# DoublePN-03092017-001.net
KiCad netlist of a schematic drawn in EAGLE
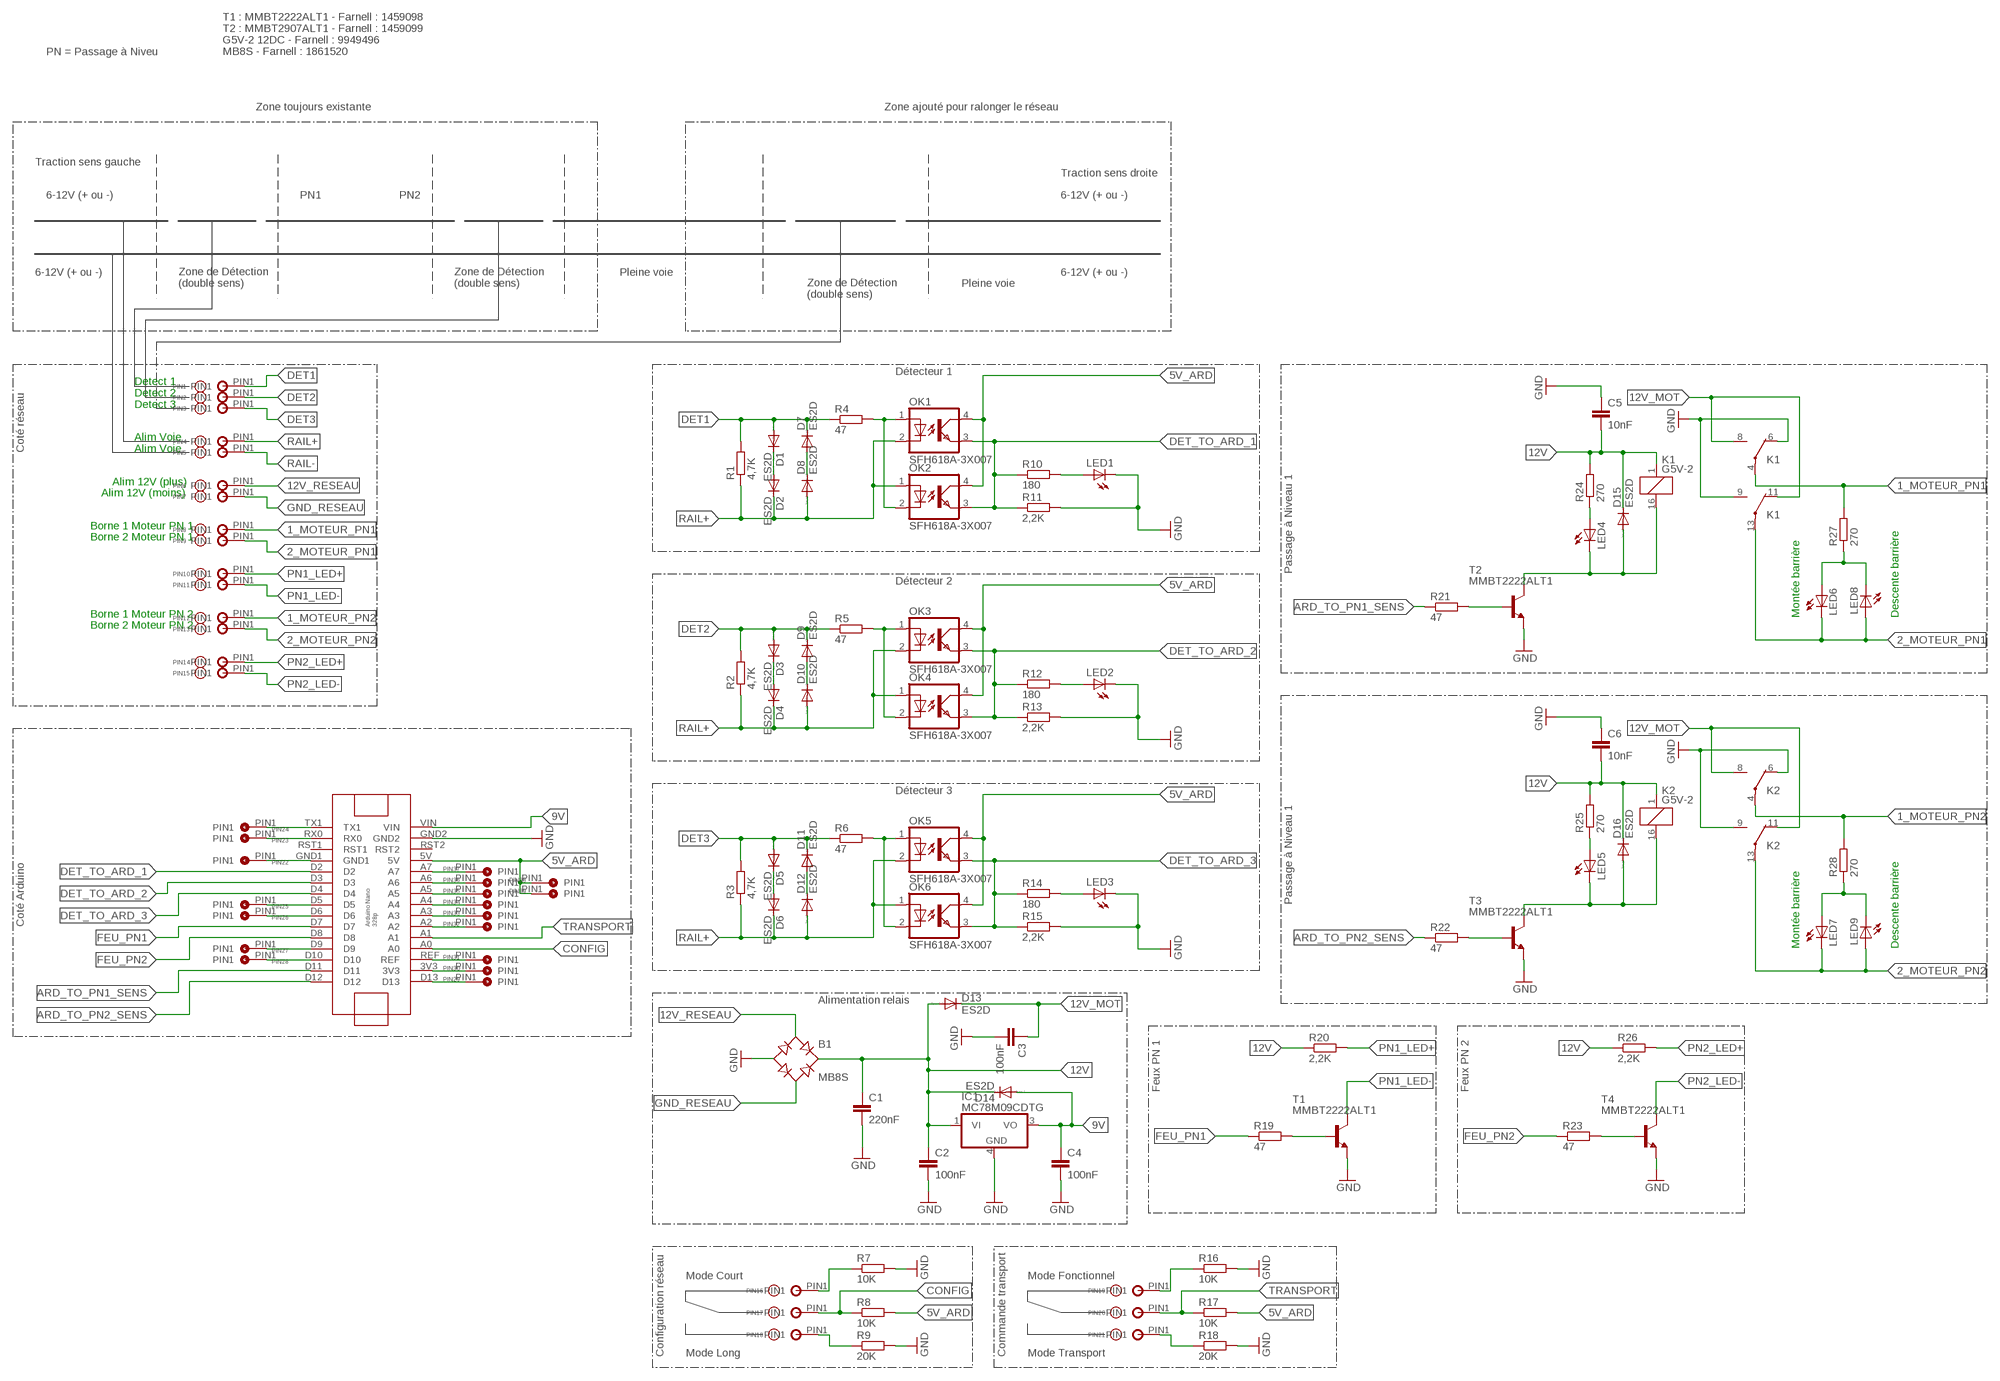
[diagram p0: schematic, sheet 1]

(export (version "E")
  (design (tool "Eeschema 10.0.6"))
  (components
    (comp (ref "ARDUINO-NANO1")
      (value "ARDUINO-NANO")
      (footprint "eagle-import:ARDUINO-NANO")
      (libsource (lib "eagle-import") (part "ARDUINO-NANO"))
    )
    (comp (ref "B1")
      (value "MB8S")
      (footprint "eagle-import:SOIC-4")
      (libsource (lib "eagle-import") (part "MBS8"))
    )
    (comp (ref "C1")
      (value "220nF")
      (footprint "eagle-import:C0805")
      (libsource (lib "eagle-import") (part "C-EUC0805"))
    )
    (comp (ref "C2")
      (value "100nF")
      (footprint "eagle-import:C0805")
      (libsource (lib "eagle-import") (part "C-EUC0805"))
    )
    (comp (ref "C3")
      (value "100nF")
      (footprint "eagle-import:C0805")
      (libsource (lib "eagle-import") (part "C-EUC0805"))
    )
    (comp (ref "C4")
      (value "100nF")
      (footprint "eagle-import:C0805")
      (libsource (lib "eagle-import") (part "C-EUC0805"))
    )
    (comp (ref "C5")
      (value "10nF")
      (footprint "eagle-import:C0805")
      (libsource (lib "eagle-import") (part "C-EUC0805"))
    )
    (comp (ref "C6")
      (value "10nF")
      (footprint "eagle-import:C0805")
      (libsource (lib "eagle-import") (part "C-EUC0805"))
    )
    (comp (ref "D1")
      (value "ES2D")
      (footprint "eagle-import:SMB")
      (libsource (lib "eagle-import") (part "ES2D"))
    )
    (comp (ref "D2")
      (value "ES2D")
      (footprint "eagle-import:SMB")
      (libsource (lib "eagle-import") (part "ES2D"))
    )
    (comp (ref "D3")
      (value "ES2D")
      (footprint "eagle-import:SMB")
      (libsource (lib "eagle-import") (part "ES2D"))
    )
    (comp (ref "D4")
      (value "ES2D")
      (footprint "eagle-import:SMB")
      (libsource (lib "eagle-import") (part "ES2D"))
    )
    (comp (ref "D5")
      (value "ES2D")
      (footprint "eagle-import:SMB")
      (libsource (lib "eagle-import") (part "ES2D"))
    )
    (comp (ref "D6")
      (value "ES2D")
      (footprint "eagle-import:SMB")
      (libsource (lib "eagle-import") (part "ES2D"))
    )
    (comp (ref "D7")
      (value "ES2D")
      (footprint "eagle-import:SMB")
      (libsource (lib "eagle-import") (part "ES2D"))
    )
    (comp (ref "D8")
      (value "ES2D")
      (footprint "eagle-import:SMB")
      (libsource (lib "eagle-import") (part "ES2D"))
    )
    (comp (ref "D9")
      (value "ES2D")
      (footprint "eagle-import:SMB")
      (libsource (lib "eagle-import") (part "ES2D"))
    )
    (comp (ref "D10")
      (value "ES2D")
      (footprint "eagle-import:SMB")
      (libsource (lib "eagle-import") (part "ES2D"))
    )
    (comp (ref "D11")
      (value "ES2D")
      (footprint "eagle-import:SMB")
      (libsource (lib "eagle-import") (part "ES2D"))
    )
    (comp (ref "D12")
      (value "ES2D")
      (footprint "eagle-import:SMB")
      (libsource (lib "eagle-import") (part "ES2D"))
    )
    (comp (ref "D13")
      (value "ES2D")
      (footprint "eagle-import:SMB")
      (libsource (lib "eagle-import") (part "ES2D"))
    )
    (comp (ref "D14")
      (value "ES2D")
      (footprint "eagle-import:SMB")
      (libsource (lib "eagle-import") (part "ES2D"))
    )
    (comp (ref "D15")
      (value "ES2D")
      (footprint "eagle-import:SMB")
      (libsource (lib "eagle-import") (part "ES2D"))
    )
    (comp (ref "D16")
      (value "ES2D")
      (footprint "eagle-import:SMB")
      (libsource (lib "eagle-import") (part "ES2D"))
    )
    (comp (ref "IC1")
      (value "MC78M09CDTG")
      (footprint "eagle-import:DPACK_3")
      (libsource (lib "eagle-import") (part "MC78M09CDTG"))
    )
    (comp (ref "K1")
      (value "G5V-2")
      (footprint "eagle-import:G5V-2")
      (fields (field (name "MPN") "G5V-2 5DC"))
      (libsource (lib "eagle-import") (part "G5V-2"))
    )
    (comp (ref "K2")
      (value "G5V-2")
      (footprint "eagle-import:G5V-2")
      (fields (field (name "MPN") "G5V-2 5DC"))
      (libsource (lib "eagle-import") (part "G5V-2"))
    )
    (comp (ref "LED1")
      (value "LEDCHIPLED_0805")
      (footprint "eagle-import:CHIPLED_0805")
      (libsource (lib "eagle-import") (part "LEDCHIPLED_0805"))
    )
    (comp (ref "LED2")
      (value "LEDCHIPLED_0805")
      (footprint "eagle-import:CHIPLED_0805")
      (libsource (lib "eagle-import") (part "LEDCHIPLED_0805"))
    )
    (comp (ref "LED3")
      (value "LEDCHIPLED_0805")
      (footprint "eagle-import:CHIPLED_0805")
      (libsource (lib "eagle-import") (part "LEDCHIPLED_0805"))
    )
    (comp (ref "LED4")
      (value "LEDCHIPLED_0805")
      (footprint "eagle-import:CHIPLED_0805")
      (libsource (lib "eagle-import") (part "LEDCHIPLED_0805"))
    )
    (comp (ref "LED5")
      (value "LEDCHIPLED_0805")
      (footprint "eagle-import:CHIPLED_0805")
      (libsource (lib "eagle-import") (part "LEDCHIPLED_0805"))
    )
    (comp (ref "LED6")
      (value "LEDCHIPLED_0805")
      (footprint "eagle-import:CHIPLED_0805")
      (libsource (lib "eagle-import") (part "LEDCHIPLED_0805"))
    )
    (comp (ref "LED7")
      (value "LEDCHIPLED_0805")
      (footprint "eagle-import:CHIPLED_0805")
      (libsource (lib "eagle-import") (part "LEDCHIPLED_0805"))
    )
    (comp (ref "LED8")
      (value "LEDCHIPLED_0805")
      (footprint "eagle-import:CHIPLED_0805")
      (libsource (lib "eagle-import") (part "LEDCHIPLED_0805"))
    )
    (comp (ref "LED9")
      (value "LEDCHIPLED_0805")
      (footprint "eagle-import:CHIPLED_0805")
      (libsource (lib "eagle-import") (part "LEDCHIPLED_0805"))
    )
    (comp (ref "OK1")
      (value "SFH618A-3X007")
      (footprint "eagle-import:SMD4-7")
      (libsource (lib "eagle-import") (part "SFH618?A-3X007"))
    )
    (comp (ref "OK2")
      (value "SFH618A-3X007")
      (footprint "eagle-import:SMD4-7")
      (libsource (lib "eagle-import") (part "SFH618?A-3X007"))
    )
    (comp (ref "OK3")
      (value "SFH618A-3X007")
      (footprint "eagle-import:SMD4-7")
      (libsource (lib "eagle-import") (part "SFH618?A-3X007"))
    )
    (comp (ref "OK4")
      (value "SFH618A-3X007")
      (footprint "eagle-import:SMD4-7")
      (libsource (lib "eagle-import") (part "SFH618?A-3X007"))
    )
    (comp (ref "OK5")
      (value "SFH618A-3X007")
      (footprint "eagle-import:SMD4-7")
      (libsource (lib "eagle-import") (part "SFH618?A-3X007"))
    )
    (comp (ref "OK6")
      (value "SFH618A-3X007")
      (footprint "eagle-import:SMD4-7")
      (libsource (lib "eagle-import") (part "SFH618?A-3X007"))
    )
    (comp (ref "PIN1")
      (value "CON-FILTRAVERSANT-1FILTRAVERSANT-1")
      (footprint "eagle-import:CON-FILTRAVERSANT-1")
      (libsource (lib "eagle-import") (part "CON-FILTRAVERSANT-1FILTRAVERSANT-1"))
    )
    (comp (ref "PIN2")
      (value "CON-FILTRAVERSANT-1FILTRAVERSANT-1")
      (footprint "eagle-import:CON-FILTRAVERSANT-1")
      (libsource (lib "eagle-import") (part "CON-FILTRAVERSANT-1FILTRAVERSANT-1"))
    )
    (comp (ref "PIN3")
      (value "CON-FILTRAVERSANT-1FILTRAVERSANT-1")
      (footprint "eagle-import:CON-FILTRAVERSANT-1")
      (libsource (lib "eagle-import") (part "CON-FILTRAVERSANT-1FILTRAVERSANT-1"))
    )
    (comp (ref "PIN4")
      (value "CON-FILTRAVERSANT-1FILTRAVERSANT-1")
      (footprint "eagle-import:CON-FILTRAVERSANT-1")
      (libsource (lib "eagle-import") (part "CON-FILTRAVERSANT-1FILTRAVERSANT-1"))
    )
    (comp (ref "PIN5")
      (value "CON-FILTRAVERSANT-1FILTRAVERSANT-1")
      (footprint "eagle-import:CON-FILTRAVERSANT-1")
      (libsource (lib "eagle-import") (part "CON-FILTRAVERSANT-1FILTRAVERSANT-1"))
    )
    (comp (ref "PIN6")
      (value "CON-FILTRAVERSANT-1FILTRAVERSANT-1")
      (footprint "eagle-import:CON-FILTRAVERSANT-1")
      (libsource (lib "eagle-import") (part "CON-FILTRAVERSANT-1FILTRAVERSANT-1"))
    )
    (comp (ref "PIN7")
      (value "CON-FILTRAVERSANT-1FILTRAVERSANT-1")
      (footprint "eagle-import:CON-FILTRAVERSANT-1")
      (libsource (lib "eagle-import") (part "CON-FILTRAVERSANT-1FILTRAVERSANT-1"))
    )
    (comp (ref "PIN8")
      (value "CON-FILTRAVERSANT-1FILTRAVERSANT-1")
      (footprint "eagle-import:CON-FILTRAVERSANT-1")
      (libsource (lib "eagle-import") (part "CON-FILTRAVERSANT-1FILTRAVERSANT-1"))
    )
    (comp (ref "PIN9")
      (value "CON-FILTRAVERSANT-1FILTRAVERSANT-1")
      (footprint "eagle-import:CON-FILTRAVERSANT-1")
      (libsource (lib "eagle-import") (part "CON-FILTRAVERSANT-1FILTRAVERSANT-1"))
    )
    (comp (ref "PIN10")
      (value "CON-FILTRAVERSANT-1FILTRAVERSANT-1")
      (footprint "eagle-import:CON-FILTRAVERSANT-1")
      (libsource (lib "eagle-import") (part "CON-FILTRAVERSANT-1FILTRAVERSANT-1"))
    )
    (comp (ref "PIN11")
      (value "CON-FILTRAVERSANT-1FILTRAVERSANT-1")
      (footprint "eagle-import:CON-FILTRAVERSANT-1")
      (libsource (lib "eagle-import") (part "CON-FILTRAVERSANT-1FILTRAVERSANT-1"))
    )
    (comp (ref "PIN12")
      (value "CON-FILTRAVERSANT-1FILTRAVERSANT-1")
      (footprint "eagle-import:CON-FILTRAVERSANT-1")
      (libsource (lib "eagle-import") (part "CON-FILTRAVERSANT-1FILTRAVERSANT-1"))
    )
    (comp (ref "PIN13")
      (value "CON-FILTRAVERSANT-1FILTRAVERSANT-1")
      (footprint "eagle-import:CON-FILTRAVERSANT-1")
      (libsource (lib "eagle-import") (part "CON-FILTRAVERSANT-1FILTRAVERSANT-1"))
    )
    (comp (ref "PIN14")
      (value "CON-FILTRAVERSANT-1FILTRAVERSANT-1")
      (footprint "eagle-import:CON-FILTRAVERSANT-1")
      (libsource (lib "eagle-import") (part "CON-FILTRAVERSANT-1FILTRAVERSANT-1"))
    )
    (comp (ref "PIN15")
      (value "CON-FILTRAVERSANT-1FILTRAVERSANT-1")
      (footprint "eagle-import:CON-FILTRAVERSANT-1")
      (libsource (lib "eagle-import") (part "CON-FILTRAVERSANT-1FILTRAVERSANT-1"))
    )
    (comp (ref "PIN16")
      (value "CON-FILTRAVERSANT-1FILTRAVERSANT-1")
      (footprint "eagle-import:CON-FILTRAVERSANT-1")
      (libsource (lib "eagle-import") (part "CON-FILTRAVERSANT-1FILTRAVERSANT-1"))
    )
    (comp (ref "PIN17")
      (value "CON-FILTRAVERSANT-1FILTRAVERSANT-1")
      (footprint "eagle-import:CON-FILTRAVERSANT-1")
      (libsource (lib "eagle-import") (part "CON-FILTRAVERSANT-1FILTRAVERSANT-1"))
    )
    (comp (ref "PIN18")
      (value "CON-FILTRAVERSANT-1FILTRAVERSANT-1")
      (footprint "eagle-import:CON-FILTRAVERSANT-1")
      (libsource (lib "eagle-import") (part "CON-FILTRAVERSANT-1FILTRAVERSANT-1"))
    )
    (comp (ref "PIN19")
      (value "CON-FILTRAVERSANT-1FILTRAVERSANT-1")
      (footprint "eagle-import:CON-FILTRAVERSANT-1")
      (libsource (lib "eagle-import") (part "CON-FILTRAVERSANT-1FILTRAVERSANT-1"))
    )
    (comp (ref "PIN20")
      (value "CON-FILTRAVERSANT-1FILTRAVERSANT-1")
      (footprint "eagle-import:CON-FILTRAVERSANT-1")
      (libsource (lib "eagle-import") (part "CON-FILTRAVERSANT-1FILTRAVERSANT-1"))
    )
    (comp (ref "PIN21")
      (value "CON-FILTRAVERSANT-1FILTRAVERSANT-1")
      (footprint "eagle-import:CON-FILTRAVERSANT-1")
      (libsource (lib "eagle-import") (part "CON-FILTRAVERSANT-1FILTRAVERSANT-1"))
    )
    (comp (ref "PIN22")
      (value "CON-TRAV-1PIN")
      (footprint "eagle-import:CON-TRAV-1")
      (libsource (lib "eagle-import") (part "CON-TRAV-1PIN"))
    )
    (comp (ref "PIN23")
      (value "CON-TRAV-1PIN")
      (footprint "eagle-import:CON-TRAV-1")
      (libsource (lib "eagle-import") (part "CON-TRAV-1PIN"))
    )
    (comp (ref "PIN24")
      (value "CON-TRAV-1PIN")
      (footprint "eagle-import:CON-TRAV-1")
      (libsource (lib "eagle-import") (part "CON-TRAV-1PIN"))
    )
    (comp (ref "PIN25")
      (value "CON-TRAV-1PIN")
      (footprint "eagle-import:CON-TRAV-1")
      (libsource (lib "eagle-import") (part "CON-TRAV-1PIN"))
    )
    (comp (ref "PIN26")
      (value "CON-TRAV-1PIN")
      (footprint "eagle-import:CON-TRAV-1")
      (libsource (lib "eagle-import") (part "CON-TRAV-1PIN"))
    )
    (comp (ref "PIN27")
      (value "CON-TRAV-1PIN")
      (footprint "eagle-import:CON-TRAV-1")
      (libsource (lib "eagle-import") (part "CON-TRAV-1PIN"))
    )
    (comp (ref "PIN28")
      (value "CON-TRAV-1PIN")
      (footprint "eagle-import:CON-TRAV-1")
      (libsource (lib "eagle-import") (part "CON-TRAV-1PIN"))
    )
    (comp (ref "PIN29")
      (value "CON-TRAV-1PIN")
      (footprint "eagle-import:CON-TRAV-1")
      (libsource (lib "eagle-import") (part "CON-TRAV-1PIN"))
    )
    (comp (ref "PIN30")
      (value "CON-TRAV-1PIN")
      (footprint "eagle-import:CON-TRAV-1")
      (libsource (lib "eagle-import") (part "CON-TRAV-1PIN"))
    )
    (comp (ref "PIN31")
      (value "CON-TRAV-1PIN")
      (footprint "eagle-import:CON-TRAV-1")
      (libsource (lib "eagle-import") (part "CON-TRAV-1PIN"))
    )
    (comp (ref "PIN32")
      (value "CON-TRAV-1PIN")
      (footprint "eagle-import:CON-TRAV-1")
      (libsource (lib "eagle-import") (part "CON-TRAV-1PIN"))
    )
    (comp (ref "PIN33")
      (value "CON-TRAV-1PIN")
      (footprint "eagle-import:CON-TRAV-1")
      (libsource (lib "eagle-import") (part "CON-TRAV-1PIN"))
    )
    (comp (ref "PIN34")
      (value "CON-TRAV-1PIN")
      (footprint "eagle-import:CON-TRAV-1")
      (libsource (lib "eagle-import") (part "CON-TRAV-1PIN"))
    )
    (comp (ref "PIN35")
      (value "CON-TRAV-1PIN")
      (footprint "eagle-import:CON-TRAV-1")
      (libsource (lib "eagle-import") (part "CON-TRAV-1PIN"))
    )
    (comp (ref "PIN36")
      (value "CON-TRAV-1PIN")
      (footprint "eagle-import:CON-TRAV-1")
      (libsource (lib "eagle-import") (part "CON-TRAV-1PIN"))
    )
    (comp (ref "PIN37")
      (value "CON-TRAV-1PIN")
      (footprint "eagle-import:CON-TRAV-1")
      (libsource (lib "eagle-import") (part "CON-TRAV-1PIN"))
    )
    (comp (ref "PIN38")
      (value "CON-TRAV-1PIN")
      (footprint "eagle-import:CON-TRAV-1")
      (libsource (lib "eagle-import") (part "CON-TRAV-1PIN"))
    )
    (comp (ref "PIN39")
      (value "CON-TRAV-1PIN")
      (footprint "eagle-import:CON-TRAV-1")
      (libsource (lib "eagle-import") (part "CON-TRAV-1PIN"))
    )
    (comp (ref "R1")
      (value "4,7K")
      (footprint "eagle-import:R0805")
      (libsource (lib "eagle-import") (part "R-EU_R0805"))
    )
    (comp (ref "R2")
      (value "4,7K")
      (footprint "eagle-import:R0805")
      (libsource (lib "eagle-import") (part "R-EU_R0805"))
    )
    (comp (ref "R3")
      (value "4,7K")
      (footprint "eagle-import:R0805")
      (libsource (lib "eagle-import") (part "R-EU_R0805"))
    )
    (comp (ref "R4")
      (value "47")
      (footprint "eagle-import:R0805")
      (libsource (lib "eagle-import") (part "R-EU_R0805"))
    )
    (comp (ref "R5")
      (value "47")
      (footprint "eagle-import:R0805")
      (libsource (lib "eagle-import") (part "R-EU_R0805"))
    )
    (comp (ref "R6")
      (value "47")
      (footprint "eagle-import:R0805")
      (libsource (lib "eagle-import") (part "R-EU_R0805"))
    )
    (comp (ref "R7")
      (value "10K")
      (footprint "eagle-import:R0805")
      (libsource (lib "eagle-import") (part "R-EU_R0805"))
    )
    (comp (ref "R8")
      (value "10K")
      (footprint "eagle-import:R0805")
      (libsource (lib "eagle-import") (part "R-EU_R0805"))
    )
    (comp (ref "R9")
      (value "20K")
      (footprint "eagle-import:R0805")
      (libsource (lib "eagle-import") (part "R-EU_R0805"))
    )
    (comp (ref "R10")
      (value "180")
      (footprint "eagle-import:R0805")
      (libsource (lib "eagle-import") (part "R-EU_R0805"))
    )
    (comp (ref "R11")
      (value "2,2K")
      (footprint "eagle-import:R0805")
      (libsource (lib "eagle-import") (part "R-EU_R0805"))
    )
    (comp (ref "R12")
      (value "180")
      (footprint "eagle-import:R0805")
      (libsource (lib "eagle-import") (part "R-EU_R0805"))
    )
    (comp (ref "R13")
      (value "2,2K")
      (footprint "eagle-import:R0805")
      (libsource (lib "eagle-import") (part "R-EU_R0805"))
    )
    (comp (ref "R14")
      (value "180")
      (footprint "eagle-import:R0805")
      (libsource (lib "eagle-import") (part "R-EU_R0805"))
    )
    (comp (ref "R15")
      (value "2,2K")
      (footprint "eagle-import:R0805")
      (libsource (lib "eagle-import") (part "R-EU_R0805"))
    )
    (comp (ref "R16")
      (value "10K")
      (footprint "eagle-import:R0805")
      (libsource (lib "eagle-import") (part "R-EU_R0805"))
    )
    (comp (ref "R17")
      (value "10K")
      (footprint "eagle-import:R0805")
      (libsource (lib "eagle-import") (part "R-EU_R0805"))
    )
    (comp (ref "R18")
      (value "20K")
      (footprint "eagle-import:R0805")
      (libsource (lib "eagle-import") (part "R-EU_R0805"))
    )
    (comp (ref "R19")
      (value "47")
      (footprint "eagle-import:R0805")
      (libsource (lib "eagle-import") (part "R-EU_R0805"))
    )
    (comp (ref "R20")
      (value "2,2K")
      (footprint "eagle-import:R0805")
      (libsource (lib "eagle-import") (part "R-EU_R0805"))
    )
    (comp (ref "R21")
      (value "47")
      (footprint "eagle-import:R0805")
      (libsource (lib "eagle-import") (part "R-EU_R0805"))
    )
    (comp (ref "R22")
      (value "47")
      (footprint "eagle-import:R0805")
      (libsource (lib "eagle-import") (part "R-EU_R0805"))
    )
    (comp (ref "R23")
      (value "47")
      (footprint "eagle-import:R0805")
      (libsource (lib "eagle-import") (part "R-EU_R0805"))
    )
    (comp (ref "R24")
      (value "270")
      (footprint "eagle-import:R0805")
      (libsource (lib "eagle-import") (part "R-EU_R0805"))
    )
    (comp (ref "R25")
      (value "270")
      (footprint "eagle-import:R0805")
      (libsource (lib "eagle-import") (part "R-EU_R0805"))
    )
    (comp (ref "R26")
      (value "2,2K")
      (footprint "eagle-import:R0805")
      (libsource (lib "eagle-import") (part "R-EU_R0805"))
    )
    (comp (ref "R27")
      (value "270")
      (footprint "eagle-import:R0805")
      (libsource (lib "eagle-import") (part "R-EU_R0805"))
    )
    (comp (ref "R28")
      (value "270")
      (footprint "eagle-import:R0805")
      (libsource (lib "eagle-import") (part "R-EU_R0805"))
    )
    (comp (ref "T1")
      (value "MMBT2222ALT1")
      (footprint "eagle-import:SOT23-BEC")
      (libsource (lib "eagle-import") (part "-NPN-SOT23-BECMMBT2222ALT1"))
    )
    (comp (ref "T2")
      (value "MMBT2222ALT1")
      (footprint "eagle-import:SOT23-BEC")
      (libsource (lib "eagle-import") (part "-NPN-SOT23-BECMMBT2222ALT1"))
    )
    (comp (ref "T3")
      (value "MMBT2222ALT1")
      (footprint "eagle-import:SOT23-BEC")
      (libsource (lib "eagle-import") (part "-NPN-SOT23-BECMMBT2222ALT1"))
    )
    (comp (ref "T4")
      (value "MMBT2222ALT1")
      (footprint "eagle-import:SOT23-BEC")
      (libsource (lib "eagle-import") (part "-NPN-SOT23-BECMMBT2222ALT1"))
    )
  )
  (nets
    (net (code "1") (name "1_MOTEUR_PN1") (class "Default")
      (node (ref "K1") (pin "4") (pinfunction "P_4") (pintype "passive"))
      (node (ref "PIN8") (pin "PIN1") (pinfunction "PIN1_PIN1") (pintype "bidirectional"))
      (node (ref "R27") (pin "2") (pinfunction "2_2") (pintype "passive"))
    )
    (net (code "2") (name "1_MOTEUR_PN2") (class "Default")
      (node (ref "K2") (pin "4") (pinfunction "P_4") (pintype "passive"))
      (node (ref "PIN12") (pin "PIN1") (pinfunction "PIN1_PIN1") (pintype "bidirectional"))
      (node (ref "R28") (pin "2") (pinfunction "2_2") (pintype "passive"))
    )
    (net (code "3") (name "2_MOTEUR_PN1") (class "Default")
      (node (ref "K1") (pin "13") (pinfunction "P_13") (pintype "passive"))
      (node (ref "LED6") (pin "C") (pinfunction "C_C") (pintype "passive"))
      (node (ref "LED8") (pin "A") (pinfunction "A_A") (pintype "passive"))
      (node (ref "PIN9") (pin "PIN1") (pinfunction "PIN1_PIN1") (pintype "bidirectional"))
    )
    (net (code "4") (name "2_MOTEUR_PN2") (class "Default")
      (node (ref "K2") (pin "13") (pinfunction "P_13") (pintype "passive"))
      (node (ref "LED7") (pin "C") (pinfunction "C_C") (pintype "passive"))
      (node (ref "LED9") (pin "A") (pinfunction "A_A") (pintype "passive"))
      (node (ref "PIN13") (pin "PIN1") (pinfunction "PIN1_PIN1") (pintype "bidirectional"))
    )
    (net (code "5") (name "5V_ARD") (class "Default")
      (node (ref "ARDUINO-NANO1") (pin "5V") (pinfunction "5V_5V") (pintype "bidirectional"))
      (node (ref "OK1") (pin "4") (pinfunction "COL_4") (pintype "passive"))
      (node (ref "OK2") (pin "4") (pinfunction "COL_4") (pintype "passive"))
      (node (ref "OK3") (pin "4") (pinfunction "COL_4") (pintype "passive"))
      (node (ref "OK4") (pin "4") (pinfunction "COL_4") (pintype "passive"))
      (node (ref "OK5") (pin "4") (pinfunction "COL_4") (pintype "passive"))
      (node (ref "OK6") (pin "4") (pinfunction "COL_4") (pintype "passive"))
      (node (ref "PIN38") (pin "PIN1") (pinfunction "PIN1_PIN1") (pintype "bidirectional"))
      (node (ref "PIN39") (pin "PIN1") (pinfunction "PIN1_PIN1") (pintype "bidirectional"))
      (node (ref "R17") (pin "2") (pinfunction "2_2") (pintype "passive"))
      (node (ref "R8") (pin "2") (pinfunction "2_2") (pintype "passive"))
    )
    (net (code "6") (name "9V") (class "Default")
      (node (ref "ARDUINO-NANO1") (pin "VIN") (pinfunction "VIN_VIN") (pintype "input"))
      (node (ref "C4") (pin "1") (pinfunction "1_1") (pintype "passive"))
      (node (ref "D14") (pin "A") (pinfunction "A_A") (pintype "passive"))
      (node (ref "IC1") (pin "3") (pinfunction "VO_3") (pintype "passive"))
    )
    (net (code "7") (name "12V") (class "Default")
      (node (ref "B1") (pin "+") (pinfunction "+_+") (pintype "passive"))
      (node (ref "C1") (pin "1") (pinfunction "1_1") (pintype "passive"))
      (node (ref "C2") (pin "1") (pinfunction "1_1") (pintype "passive"))
      (node (ref "C5") (pin "2") (pinfunction "2_2") (pintype "passive"))
      (node (ref "C6") (pin "2") (pinfunction "2_2") (pintype "passive"))
      (node (ref "D13") (pin "A") (pinfunction "A_A") (pintype "passive"))
      (node (ref "D14") (pin "C") (pinfunction "C_C") (pintype "passive"))
      (node (ref "D15") (pin "C") (pinfunction "C_C") (pintype "passive"))
      (node (ref "D16") (pin "C") (pinfunction "C_C") (pintype "passive"))
      (node (ref "IC1") (pin "1") (pinfunction "VI_1") (pintype "input"))
      (node (ref "K1") (pin "1") (pinfunction "1_1") (pintype "passive"))
      (node (ref "K2") (pin "1") (pinfunction "1_1") (pintype "passive"))
      (node (ref "R20") (pin "1") (pinfunction "1_1") (pintype "passive"))
      (node (ref "R24") (pin "2") (pinfunction "2_2") (pintype "passive"))
      (node (ref "R25") (pin "2") (pinfunction "2_2") (pintype "passive"))
      (node (ref "R26") (pin "1") (pinfunction "1_1") (pintype "passive"))
    )
    (net (code "8") (name "12V_MOT") (class "Default")
      (node (ref "C3") (pin "1") (pinfunction "1_1") (pintype "passive"))
      (node (ref "D13") (pin "C") (pinfunction "C_C") (pintype "passive"))
      (node (ref "K1") (pin "11") (pinfunction "O_11") (pintype "passive"))
      (node (ref "K1") (pin "8") (pinfunction "S_8") (pintype "passive"))
      (node (ref "K2") (pin "11") (pinfunction "O_11") (pintype "passive"))
      (node (ref "K2") (pin "8") (pinfunction "S_8") (pintype "passive"))
    )
    (net (code "9") (name "12V_RESEAU") (class "Default")
      (node (ref "B1") (pin "~1") (pinfunction "AC1_~1") (pintype "passive"))
      (node (ref "PIN6") (pin "PIN1") (pinfunction "PIN1_PIN1") (pintype "bidirectional"))
    )
    (net (code "10") (name "ARD_TO_PN1_SENS") (class "Default")
      (node (ref "ARDUINO-NANO1") (pin "D11") (pinfunction "D11_D11") (pintype "bidirectional"))
      (node (ref "R21") (pin "1") (pinfunction "1_1") (pintype "passive"))
    )
    (net (code "11") (name "ARD_TO_PN2_SENS") (class "Default")
      (node (ref "ARDUINO-NANO1") (pin "D12") (pinfunction "D12_D12") (pintype "bidirectional"))
      (node (ref "R22") (pin "1") (pinfunction "1_1") (pintype "passive"))
    )
    (net (code "12") (name "CONFIG") (class "Default")
      (node (ref "ARDUINO-NANO1") (pin "A0") (pinfunction "A0_A0") (pintype "bidirectional"))
      (node (ref "PIN17") (pin "PIN1") (pinfunction "PIN1_PIN1") (pintype "bidirectional"))
      (node (ref "R8") (pin "1") (pinfunction "1_1") (pintype "passive"))
    )
    (net (code "13") (name "DET1") (class "Default")
      (node (ref "D1") (pin "A") (pinfunction "A_A") (pintype "passive"))
      (node (ref "D7") (pin "C") (pinfunction "C_C") (pintype "passive"))
      (node (ref "PIN1") (pin "PIN1") (pinfunction "PIN1_PIN1") (pintype "bidirectional"))
      (node (ref "R1") (pin "2") (pinfunction "2_2") (pintype "passive"))
      (node (ref "R4") (pin "1") (pinfunction "1_1") (pintype "passive"))
    )
    (net (code "14") (name "DET2") (class "Default")
      (node (ref "D3") (pin "A") (pinfunction "A_A") (pintype "passive"))
      (node (ref "D9") (pin "C") (pinfunction "C_C") (pintype "passive"))
      (node (ref "PIN2") (pin "PIN1") (pinfunction "PIN1_PIN1") (pintype "bidirectional"))
      (node (ref "R2") (pin "2") (pinfunction "2_2") (pintype "passive"))
      (node (ref "R5") (pin "1") (pinfunction "1_1") (pintype "passive"))
    )
    (net (code "15") (name "DET3") (class "Default")
      (node (ref "D11") (pin "C") (pinfunction "C_C") (pintype "passive"))
      (node (ref "D5") (pin "A") (pinfunction "A_A") (pintype "passive"))
      (node (ref "PIN3") (pin "PIN1") (pinfunction "PIN1_PIN1") (pintype "bidirectional"))
      (node (ref "R3") (pin "2") (pinfunction "2_2") (pintype "passive"))
      (node (ref "R6") (pin "1") (pinfunction "1_1") (pintype "passive"))
    )
    (net (code "16") (name "DET_TO_ARD_1") (class "Default")
      (node (ref "ARDUINO-NANO1") (pin "D2") (pinfunction "D2_D2") (pintype "bidirectional"))
      (node (ref "OK1") (pin "3") (pinfunction "EMIT_3") (pintype "passive"))
      (node (ref "OK2") (pin "3") (pinfunction "EMIT_3") (pintype "passive"))
      (node (ref "R10") (pin "1") (pinfunction "1_1") (pintype "passive"))
      (node (ref "R11") (pin "1") (pinfunction "1_1") (pintype "passive"))
    )
    (net (code "17") (name "DET_TO_ARD_2") (class "Default")
      (node (ref "ARDUINO-NANO1") (pin "D3") (pinfunction "D3_D3") (pintype "bidirectional"))
      (node (ref "OK3") (pin "3") (pinfunction "EMIT_3") (pintype "passive"))
      (node (ref "OK4") (pin "3") (pinfunction "EMIT_3") (pintype "passive"))
      (node (ref "R12") (pin "1") (pinfunction "1_1") (pintype "passive"))
      (node (ref "R13") (pin "1") (pinfunction "1_1") (pintype "passive"))
    )
    (net (code "18") (name "DET_TO_ARD_3") (class "Default")
      (node (ref "ARDUINO-NANO1") (pin "D4") (pinfunction "D4_D4") (pintype "bidirectional"))
      (node (ref "OK5") (pin "3") (pinfunction "EMIT_3") (pintype "passive"))
      (node (ref "OK6") (pin "3") (pinfunction "EMIT_3") (pintype "passive"))
      (node (ref "R14") (pin "1") (pinfunction "1_1") (pintype "passive"))
      (node (ref "R15") (pin "1") (pinfunction "1_1") (pintype "passive"))
    )
    (net (code "19") (name "FEU_PN1") (class "Default")
      (node (ref "ARDUINO-NANO1") (pin "D7") (pinfunction "D7_D7") (pintype "bidirectional"))
      (node (ref "R19") (pin "1") (pinfunction "1_1") (pintype "passive"))
    )
    (net (code "20") (name "FEU_PN2") (class "Default")
      (node (ref "ARDUINO-NANO1") (pin "D8") (pinfunction "D8_D8") (pintype "bidirectional"))
      (node (ref "R23") (pin "1") (pinfunction "1_1") (pintype "passive"))
    )
    (net (code "21") (name "GND") (class "Default")
      (node (ref "ARDUINO-NANO1") (pin "GND2") (pinfunction "GND2_GND2") (pintype "bidirectional"))
      (node (ref "B1") (pin "-") (pinfunction "-_-") (pintype "passive"))
      (node (ref "C1") (pin "2") (pinfunction "2_2") (pintype "passive"))
      (node (ref "C2") (pin "2") (pinfunction "2_2") (pintype "passive"))
      (node (ref "C3") (pin "2") (pinfunction "2_2") (pintype "passive"))
      (node (ref "C4") (pin "2") (pinfunction "2_2") (pintype "passive"))
      (node (ref "C5") (pin "1") (pinfunction "1_1") (pintype "passive"))
      (node (ref "C6") (pin "1") (pinfunction "1_1") (pintype "passive"))
      (node (ref "IC1") (pin "4") (pinfunction "GND_4") (pintype "passive"))
      (node (ref "K1") (pin "6") (pinfunction "O_6") (pintype "passive"))
      (node (ref "K1") (pin "9") (pinfunction "S_9") (pintype "passive"))
      (node (ref "K2") (pin "6") (pinfunction "O_6") (pintype "passive"))
      (node (ref "K2") (pin "9") (pinfunction "S_9") (pintype "passive"))
      (node (ref "LED1") (pin "C") (pinfunction "C_C") (pintype "passive"))
      (node (ref "LED2") (pin "C") (pinfunction "C_C") (pintype "passive"))
      (node (ref "LED3") (pin "C") (pinfunction "C_C") (pintype "passive"))
      (node (ref "R11") (pin "2") (pinfunction "2_2") (pintype "passive"))
      (node (ref "R13") (pin "2") (pinfunction "2_2") (pintype "passive"))
      (node (ref "R15") (pin "2") (pinfunction "2_2") (pintype "passive"))
      (node (ref "R16") (pin "2") (pinfunction "2_2") (pintype "passive"))
      (node (ref "R18") (pin "2") (pinfunction "2_2") (pintype "passive"))
      (node (ref "R7") (pin "2") (pinfunction "2_2") (pintype "passive"))
      (node (ref "R9") (pin "2") (pinfunction "2_2") (pintype "passive"))
      (node (ref "T1") (pin "E") (pinfunction "E_E") (pintype "passive"))
      (node (ref "T2") (pin "E") (pinfunction "E_E") (pintype "passive"))
      (node (ref "T3") (pin "E") (pinfunction "E_E") (pintype "passive"))
      (node (ref "T4") (pin "E") (pinfunction "E_E") (pintype "passive"))
    )
    (net (code "22") (name "GND_RESEAU") (class "Default")
      (node (ref "B1") (pin "~2") (pinfunction "AC2_~2") (pintype "passive"))
      (node (ref "PIN7") (pin "PIN1") (pinfunction "PIN1_PIN1") (pintype "bidirectional"))
    )
    (net (code "23") (name "Net-(ARDUINO-NANO1-Pad3V3)") (class "Default")
      (node (ref "ARDUINO-NANO1") (pin "3V3") (pinfunction "3V3_3V3") (pintype "output"))
      (node (ref "PIN30") (pin "PIN1") (pinfunction "PIN1_PIN1") (pintype "bidirectional"))
    )
    (net (code "24") (name "Net-(ARDUINO-NANO1-PadA2)") (class "Default")
      (node (ref "ARDUINO-NANO1") (pin "A2") (pinfunction "A2_A2") (pintype "bidirectional"))
      (node (ref "PIN32") (pin "PIN1") (pinfunction "PIN1_PIN1") (pintype "bidirectional"))
    )
    (net (code "25") (name "Net-(ARDUINO-NANO1-PadA3)") (class "Default")
      (node (ref "ARDUINO-NANO1") (pin "A3") (pinfunction "A3_A3") (pintype "bidirectional"))
      (node (ref "PIN33") (pin "PIN1") (pinfunction "PIN1_PIN1") (pintype "bidirectional"))
    )
    (net (code "26") (name "Net-(ARDUINO-NANO1-PadA4)") (class "Default")
      (node (ref "ARDUINO-NANO1") (pin "A4") (pinfunction "A4_A4") (pintype "bidirectional"))
      (node (ref "PIN34") (pin "PIN1") (pinfunction "PIN1_PIN1") (pintype "bidirectional"))
    )
    (net (code "27") (name "Net-(ARDUINO-NANO1-PadA5)") (class "Default")
      (node (ref "ARDUINO-NANO1") (pin "A5") (pinfunction "A5_A5") (pintype "bidirectional"))
      (node (ref "PIN35") (pin "PIN1") (pinfunction "PIN1_PIN1") (pintype "bidirectional"))
    )
    (net (code "28") (name "Net-(ARDUINO-NANO1-PadA6)") (class "Default")
      (node (ref "ARDUINO-NANO1") (pin "A6") (pinfunction "A6_A6") (pintype "bidirectional"))
      (node (ref "PIN36") (pin "PIN1") (pinfunction "PIN1_PIN1") (pintype "bidirectional"))
    )
    (net (code "29") (name "Net-(ARDUINO-NANO1-PadA7)") (class "Default")
      (node (ref "ARDUINO-NANO1") (pin "A7") (pinfunction "A7_A7") (pintype "output"))
      (node (ref "PIN37") (pin "PIN1") (pinfunction "PIN1_PIN1") (pintype "bidirectional"))
    )
    (net (code "30") (name "Net-(ARDUINO-NANO1-PadD5)") (class "Default")
      (node (ref "ARDUINO-NANO1") (pin "D5") (pinfunction "D5_D5") (pintype "bidirectional"))
      (node (ref "PIN25") (pin "PIN1") (pinfunction "PIN1_PIN1") (pintype "bidirectional"))
    )
    (net (code "31") (name "Net-(ARDUINO-NANO1-PadD6)") (class "Default")
      (node (ref "ARDUINO-NANO1") (pin "D6") (pinfunction "D6_D6") (pintype "bidirectional"))
      (node (ref "PIN26") (pin "PIN1") (pinfunction "PIN1_PIN1") (pintype "bidirectional"))
    )
    (net (code "32") (name "Net-(ARDUINO-NANO1-PadD9)") (class "Default")
      (node (ref "ARDUINO-NANO1") (pin "D9") (pinfunction "D9_D9") (pintype "bidirectional"))
      (node (ref "PIN27") (pin "PIN1") (pinfunction "PIN1_PIN1") (pintype "bidirectional"))
    )
    (net (code "33") (name "Net-(ARDUINO-NANO1-PadD10)") (class "Default")
      (node (ref "ARDUINO-NANO1") (pin "D10") (pinfunction "D10_D10") (pintype "bidirectional"))
      (node (ref "PIN28") (pin "PIN1") (pinfunction "PIN1_PIN1") (pintype "bidirectional"))
    )
    (net (code "34") (name "Net-(ARDUINO-NANO1-PadD13)") (class "Default")
      (node (ref "ARDUINO-NANO1") (pin "D13") (pinfunction "D13_D13") (pintype "bidirectional"))
      (node (ref "PIN29") (pin "PIN1") (pinfunction "PIN1_PIN1") (pintype "bidirectional"))
    )
    (net (code "35") (name "Net-(ARDUINO-NANO1-PadGND1)") (class "Default")
      (node (ref "ARDUINO-NANO1") (pin "GND1") (pinfunction "GND1_GND1") (pintype "input"))
      (node (ref "PIN22") (pin "PIN1") (pinfunction "PIN1_PIN1") (pintype "bidirectional"))
    )
    (net (code "36") (name "Net-(ARDUINO-NANO1-PadREF)") (class "Default")
      (node (ref "ARDUINO-NANO1") (pin "REF") (pinfunction "REF_REF") (pintype "output"))
      (node (ref "PIN31") (pin "PIN1") (pinfunction "PIN1_PIN1") (pintype "bidirectional"))
    )
    (net (code "37") (name "Net-(ARDUINO-NANO1-PadRX0)") (class "Default")
      (node (ref "ARDUINO-NANO1") (pin "RX0") (pinfunction "RX0_RX0") (pintype "input"))
      (node (ref "PIN23") (pin "PIN1") (pinfunction "PIN1_PIN1") (pintype "bidirectional"))
    )
    (net (code "38") (name "Net-(ARDUINO-NANO1-PadTX1)") (class "Default")
      (node (ref "ARDUINO-NANO1") (pin "TX1") (pinfunction "TX1_TX1") (pintype "output"))
      (node (ref "PIN24") (pin "PIN1") (pinfunction "PIN1_PIN1") (pintype "bidirectional"))
    )
    (net (code "39") (name "Net-(D1-PadC)") (class "Default")
      (node (ref "D1") (pin "C") (pinfunction "C_C") (pintype "passive"))
      (node (ref "D2") (pin "A") (pinfunction "A_A") (pintype "passive"))
    )
    (net (code "40") (name "Net-(D3-PadC)") (class "Default")
      (node (ref "D3") (pin "C") (pinfunction "C_C") (pintype "passive"))
      (node (ref "D4") (pin "A") (pinfunction "A_A") (pintype "passive"))
    )
    (net (code "41") (name "Net-(D5-PadC)") (class "Default")
      (node (ref "D5") (pin "C") (pinfunction "C_C") (pintype "passive"))
      (node (ref "D6") (pin "A") (pinfunction "A_A") (pintype "passive"))
    )
    (net (code "42") (name "Net-(D7-PadA)") (class "Default")
      (node (ref "D7") (pin "A") (pinfunction "A_A") (pintype "passive"))
      (node (ref "D8") (pin "C") (pinfunction "C_C") (pintype "passive"))
    )
    (net (code "43") (name "Net-(D10-PadC)") (class "Default")
      (node (ref "D10") (pin "C") (pinfunction "C_C") (pintype "passive"))
      (node (ref "D9") (pin "A") (pinfunction "A_A") (pintype "passive"))
    )
    (net (code "44") (name "Net-(D11-PadA)") (class "Default")
      (node (ref "D11") (pin "A") (pinfunction "A_A") (pintype "passive"))
      (node (ref "D12") (pin "C") (pinfunction "C_C") (pintype "passive"))
    )
    (net (code "45") (name "Net-(K1C-2)") (class "Default")
      (node (ref "D15") (pin "A") (pinfunction "A_A") (pintype "passive"))
      (node (ref "K1") (pin "16") (pinfunction "2_16") (pintype "passive"))
      (node (ref "LED4") (pin "C") (pinfunction "C_C") (pintype "passive"))
      (node (ref "T2") (pin "C") (pinfunction "C_C") (pintype "passive"))
    )
    (net (code "46") (name "Net-(K2C-2)") (class "Default")
      (node (ref "D16") (pin "A") (pinfunction "A_A") (pintype "passive"))
      (node (ref "K2") (pin "16") (pinfunction "2_16") (pintype "passive"))
      (node (ref "LED5") (pin "C") (pinfunction "C_C") (pintype "passive"))
      (node (ref "T3") (pin "C") (pinfunction "C_C") (pintype "passive"))
    )
    (net (code "47") (name "Net-(LED1-PadA)") (class "Default")
      (node (ref "LED1") (pin "A") (pinfunction "A_A") (pintype "passive"))
      (node (ref "R10") (pin "2") (pinfunction "2_2") (pintype "passive"))
    )
    (net (code "48") (name "Net-(LED2-PadA)") (class "Default")
      (node (ref "LED2") (pin "A") (pinfunction "A_A") (pintype "passive"))
      (node (ref "R12") (pin "2") (pinfunction "2_2") (pintype "passive"))
    )
    (net (code "49") (name "Net-(LED3-PadA)") (class "Default")
      (node (ref "LED3") (pin "A") (pinfunction "A_A") (pintype "passive"))
      (node (ref "R14") (pin "2") (pinfunction "2_2") (pintype "passive"))
    )
    (net (code "50") (name "Net-(LED4-PadA)") (class "Default")
      (node (ref "LED4") (pin "A") (pinfunction "A_A") (pintype "passive"))
      (node (ref "R24") (pin "1") (pinfunction "1_1") (pintype "passive"))
    )
    (net (code "51") (name "Net-(LED5-PadA)") (class "Default")
      (node (ref "LED5") (pin "A") (pinfunction "A_A") (pintype "passive"))
      (node (ref "R25") (pin "1") (pinfunction "1_1") (pintype "passive"))
    )
    (net (code "52") (name "Net-(LED6-PadA)") (class "Default")
      (node (ref "LED6") (pin "A") (pinfunction "A_A") (pintype "passive"))
      (node (ref "LED8") (pin "C") (pinfunction "C_C") (pintype "passive"))
      (node (ref "R27") (pin "1") (pinfunction "1_1") (pintype "passive"))
    )
    (net (code "53") (name "Net-(LED7-PadA)") (class "Default")
      (node (ref "LED7") (pin "A") (pinfunction "A_A") (pintype "passive"))
      (node (ref "LED9") (pin "C") (pinfunction "C_C") (pintype "passive"))
      (node (ref "R28") (pin "1") (pinfunction "1_1") (pintype "passive"))
    )
    (net (code "54") (name "Net-(OK1-A)") (class "Default")
      (node (ref "OK1") (pin "1") (pinfunction "A_1") (pintype "passive"))
      (node (ref "OK2") (pin "2") (pinfunction "C_2") (pintype "passive"))
      (node (ref "R4") (pin "2") (pinfunction "2_2") (pintype "passive"))
    )
    (net (code "55") (name "Net-(OK3-A)") (class "Default")
      (node (ref "OK3") (pin "1") (pinfunction "A_1") (pintype "passive"))
      (node (ref "OK4") (pin "2") (pinfunction "C_2") (pintype "passive"))
      (node (ref "R5") (pin "2") (pinfunction "2_2") (pintype "passive"))
    )
    (net (code "56") (name "Net-(OK5-A)") (class "Default")
      (node (ref "OK5") (pin "1") (pinfunction "A_1") (pintype "passive"))
      (node (ref "OK6") (pin "2") (pinfunction "C_2") (pintype "passive"))
      (node (ref "R6") (pin "2") (pinfunction "2_2") (pintype "passive"))
    )
    (net (code "57") (name "Net-(PIN16-PadPIN1)") (class "Default")
      (node (ref "PIN16") (pin "PIN1") (pinfunction "PIN1_PIN1") (pintype "bidirectional"))
      (node (ref "R7") (pin "1") (pinfunction "1_1") (pintype "passive"))
    )
    (net (code "58") (name "Net-(PIN18-PadPIN1)") (class "Default")
      (node (ref "PIN18") (pin "PIN1") (pinfunction "PIN1_PIN1") (pintype "bidirectional"))
      (node (ref "R9") (pin "1") (pinfunction "1_1") (pintype "passive"))
    )
    (net (code "59") (name "Net-(PIN19-PadPIN1)") (class "Default")
      (node (ref "PIN19") (pin "PIN1") (pinfunction "PIN1_PIN1") (pintype "bidirectional"))
      (node (ref "R16") (pin "1") (pinfunction "1_1") (pintype "passive"))
    )
    (net (code "60") (name "Net-(PIN21-PadPIN1)") (class "Default")
      (node (ref "PIN21") (pin "PIN1") (pinfunction "PIN1_PIN1") (pintype "bidirectional"))
      (node (ref "R18") (pin "1") (pinfunction "1_1") (pintype "passive"))
    )
    (net (code "61") (name "Net-(R19-Pad2)") (class "Default")
      (node (ref "R19") (pin "2") (pinfunction "2_2") (pintype "passive"))
      (node (ref "T1") (pin "B") (pinfunction "B_B") (pintype "passive"))
    )
    (net (code "62") (name "Net-(R21-Pad2)") (class "Default")
      (node (ref "R21") (pin "2") (pinfunction "2_2") (pintype "passive"))
      (node (ref "T2") (pin "B") (pinfunction "B_B") (pintype "passive"))
    )
    (net (code "63") (name "Net-(R22-Pad2)") (class "Default")
      (node (ref "R22") (pin "2") (pinfunction "2_2") (pintype "passive"))
      (node (ref "T3") (pin "B") (pinfunction "B_B") (pintype "passive"))
    )
    (net (code "64") (name "Net-(R23-Pad2)") (class "Default")
      (node (ref "R23") (pin "2") (pinfunction "2_2") (pintype "passive"))
      (node (ref "T4") (pin "B") (pinfunction "B_B") (pintype "passive"))
    )
    (net (code "65") (name "PN1_LED+") (class "Default")
      (node (ref "PIN10") (pin "PIN1") (pinfunction "PIN1_PIN1") (pintype "bidirectional"))
      (node (ref "R20") (pin "2") (pinfunction "2_2") (pintype "passive"))
    )
    (net (code "66") (name "PN1_LED-") (class "Default")
      (node (ref "PIN11") (pin "PIN1") (pinfunction "PIN1_PIN1") (pintype "bidirectional"))
      (node (ref "T1") (pin "C") (pinfunction "C_C") (pintype "passive"))
    )
    (net (code "67") (name "PN2_LED+") (class "Default")
      (node (ref "PIN14") (pin "PIN1") (pinfunction "PIN1_PIN1") (pintype "bidirectional"))
      (node (ref "R26") (pin "2") (pinfunction "2_2") (pintype "passive"))
    )
    (net (code "68") (name "PN2_LED-") (class "Default")
      (node (ref "PIN15") (pin "PIN1") (pinfunction "PIN1_PIN1") (pintype "bidirectional"))
      (node (ref "T4") (pin "C") (pinfunction "C_C") (pintype "passive"))
    )
    (net (code "69") (name "RAIL+") (class "Default")
      (node (ref "D10") (pin "A") (pinfunction "A_A") (pintype "passive"))
      (node (ref "D12") (pin "A") (pinfunction "A_A") (pintype "passive"))
      (node (ref "D2") (pin "C") (pinfunction "C_C") (pintype "passive"))
      (node (ref "D4") (pin "C") (pinfunction "C_C") (pintype "passive"))
      (node (ref "D6") (pin "C") (pinfunction "C_C") (pintype "passive"))
      (node (ref "D8") (pin "A") (pinfunction "A_A") (pintype "passive"))
      (node (ref "OK1") (pin "2") (pinfunction "C_2") (pintype "passive"))
      (node (ref "OK2") (pin "1") (pinfunction "A_1") (pintype "passive"))
      (node (ref "OK3") (pin "2") (pinfunction "C_2") (pintype "passive"))
      (node (ref "OK4") (pin "1") (pinfunction "A_1") (pintype "passive"))
      (node (ref "OK5") (pin "2") (pinfunction "C_2") (pintype "passive"))
      (node (ref "OK6") (pin "1") (pinfunction "A_1") (pintype "passive"))
      (node (ref "PIN4") (pin "PIN1") (pinfunction "PIN1_PIN1") (pintype "bidirectional"))
      (node (ref "R1") (pin "1") (pinfunction "1_1") (pintype "passive"))
      (node (ref "R2") (pin "1") (pinfunction "1_1") (pintype "passive"))
      (node (ref "R3") (pin "1") (pinfunction "1_1") (pintype "passive"))
    )
    (net (code "70") (name "RAIL-") (class "Default")
      (node (ref "PIN5") (pin "PIN1") (pinfunction "PIN1_PIN1") (pintype "bidirectional"))
    )
    (net (code "71") (name "TRANSPORT") (class "Default")
      (node (ref "ARDUINO-NANO1") (pin "A1") (pinfunction "A1_A1") (pintype "bidirectional"))
      (node (ref "PIN20") (pin "PIN1") (pinfunction "PIN1_PIN1") (pintype "bidirectional"))
      (node (ref "R17") (pin "1") (pinfunction "1_1") (pintype "passive"))
    )
    (net (code "72") (name "unconnected-(ARDUINO-NANO1-PadRST1)") (class "Default")
      (node (ref "ARDUINO-NANO1") (pin "RST1") (pinfunction "RST1_RST1") (pintype "input"))
    )
    (net (code "73") (name "unconnected-(ARDUINO-NANO1-PadRST2)") (class "Default")
      (node (ref "ARDUINO-NANO1") (pin "RST2") (pinfunction "RST2_RST2") (pintype "bidirectional"))
    )
  )
)
